# usb_converter.net
KiCad netlist of a schematic drawn in Altium Designer
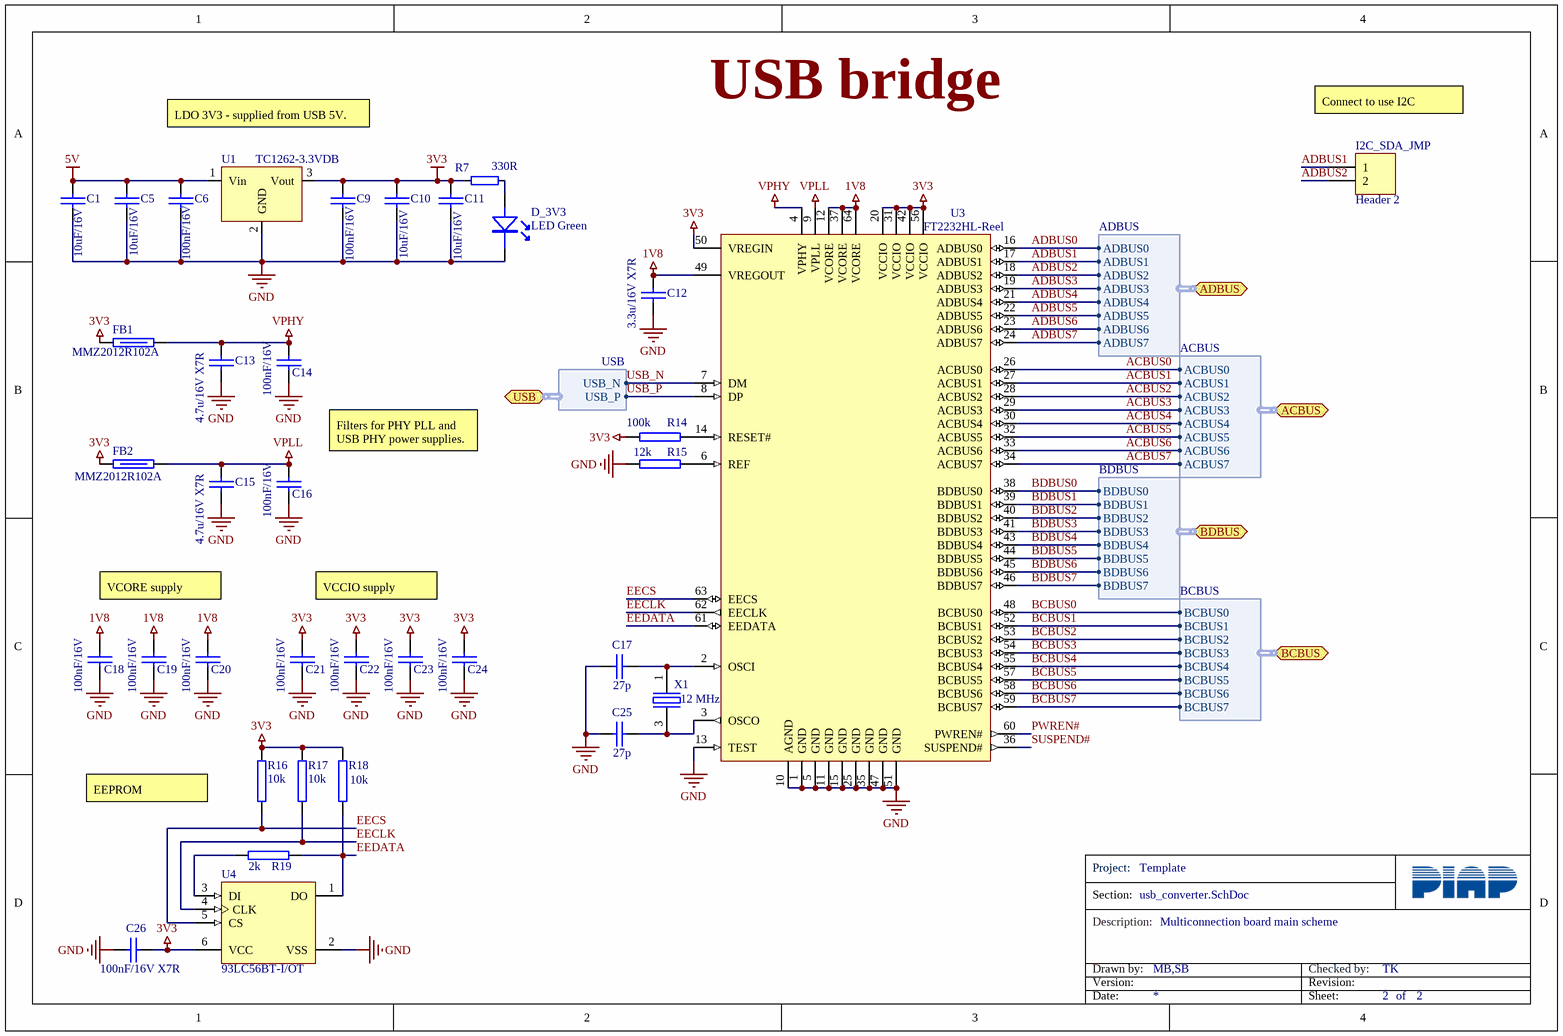
[diagram p0: usb_converter.SchDoc]

(export (version "E")
  (design (tool "Eeschema 10.0.6"))
  (components
    (comp (ref "C1")
      (value "10uF/16V")
      (footprint "packages:0603")
      (description "10uF,16V,0603,X5R, 10%")
      (fields (field (name "TOLERANCE") "10%"))
      (libsource (lib "cap_ceramic") (part "100nF/16V/0603"))
    )
    (comp (ref "C5")
      (value "10uF/16V")
      (footprint "packages:0603")
      (description "10uF,16V,0603,X5R, 10%")
      (fields (field (name "TOLERANCE") "10%"))
      (libsource (lib "cap_ceramic") (part "100nF/16V/0603"))
    )
    (comp (ref "C6")
      (value "100nF/16V")
      (footprint "packages:0603")
      (description "100nF,16V,0603,,X7R")
      (fields (field (name "TOLERANCE") "10%"))
      (libsource (lib "cap_ceramic") (part "100nF/16V/0603"))
    )
    (comp (ref "C9")
      (value "100nF/16V")
      (footprint "packages:0603")
      (description "100nF,16V,0603,,X7R")
      (fields (field (name "TOLERANCE") "10%"))
      (libsource (lib "cap_ceramic") (part "100nF/16V/0603"))
    )
    (comp (ref "C10")
      (value "10uF/16V")
      (footprint "packages:0603")
      (description "10uF,16V,0603,X5R, 10%")
      (fields (field (name "TOLERANCE") "10%"))
      (libsource (lib "cap_ceramic") (part "100nF/16V/0603"))
    )
    (comp (ref "C11")
      (value "10uF/16V")
      (footprint "packages:0603")
      (description "10uF,16V,0603,X5R, 10%")
      (fields (field (name "TOLERANCE") "10%"))
      (libsource (lib "cap_ceramic") (part "100nF/16V/0603"))
    )
    (comp (ref "C12")
      (value "3.3u/16V X7R")
      (footprint "packages:0805")
      (description "Chip Capacitor 3.3u/16V X7R")
      (fields (field (name "EMAIL") "AGrabowska@farnell.com"))
      (libsource (lib "capacitors") (part "n100"))
    )
    (comp (ref "C13")
      (value "4.7u/16V X7R")
      (footprint "packages:0805")
      (description "Chip Capacitor 4.7u/16V X7R")
      (fields (field (name "EMAIL") "AGrabowska@farnell.com"))
      (libsource (lib "capacitors") (part "n100"))
    )
    (comp (ref "C14")
      (value "100nF/16V")
      (footprint "packages:0603")
      (description "NS")
      (fields (field (name "EMAIL") "AGrabowska@farnell.com"))
      (libsource (lib "capacitors") (part "n100"))
    )
    (comp (ref "C15")
      (value "4.7u/16V X7R")
      (footprint "packages:0805")
      (description "Chip Capacitor 4.7u/16V X7R")
      (fields (field (name "EMAIL") "AGrabowska@farnell.com"))
      (libsource (lib "capacitors") (part "n100"))
    )
    (comp (ref "C16")
      (value "100nF/16V")
      (footprint "packages:0603")
      (description "NS")
      (fields (field (name "EMAIL") "AGrabowska@farnell.com"))
      (libsource (lib "capacitors") (part "n100"))
    )
    (comp (ref "C17")
      (value "27p")
      (footprint "packages:0603")
      (description "NS")
      (fields (field (name "EMAIL") "AGrabowska@farnell.com"))
      (libsource (lib "capacitors") (part "n100"))
    )
    (comp (ref "C18")
      (value "100nF/16V")
      (footprint "packages:0603")
      (description "NS")
      (fields (field (name "EMAIL") "AGrabowska@farnell.com"))
      (libsource (lib "capacitors") (part "n100"))
    )
    (comp (ref "C19")
      (value "100nF/16V")
      (footprint "packages:0603")
      (description "NS")
      (fields (field (name "EMAIL") "AGrabowska@farnell.com"))
      (libsource (lib "capacitors") (part "n100"))
    )
    (comp (ref "C20")
      (value "100nF/16V")
      (footprint "packages:0603")
      (description "NS")
      (fields (field (name "EMAIL") "AGrabowska@farnell.com"))
      (libsource (lib "capacitors") (part "n100"))
    )
    (comp (ref "C21")
      (value "100nF/16V")
      (footprint "packages:0603")
      (description "NS")
      (fields (field (name "EMAIL") "AGrabowska@farnell.com"))
      (libsource (lib "capacitors") (part "n100"))
    )
    (comp (ref "C22")
      (value "100nF/16V")
      (footprint "packages:0603")
      (description "NS")
      (fields (field (name "EMAIL") "AGrabowska@farnell.com"))
      (libsource (lib "capacitors") (part "n100"))
    )
    (comp (ref "C23")
      (value "100nF/16V")
      (footprint "packages:0603")
      (description "NS")
      (fields (field (name "EMAIL") "AGrabowska@farnell.com"))
      (libsource (lib "capacitors") (part "n100"))
    )
    (comp (ref "C24")
      (value "100nF/16V")
      (footprint "packages:0603")
      (description "NS")
      (fields (field (name "EMAIL") "AGrabowska@farnell.com"))
      (libsource (lib "capacitors") (part "n100"))
    )
    (comp (ref "C25")
      (value "27p")
      (footprint "packages:0603")
      (description "NS")
      (fields (field (name "EMAIL") "AGrabowska@farnell.com"))
      (libsource (lib "capacitors") (part "n100"))
    )
    (comp (ref "C26")
      (value "100nF/16V X7R")
      (footprint "packages:0805")
      (description "Chip Capacitor 100nF/16V X7R")
      (fields (field (name "EMAIL") "AGrabowska@farnell.com"))
      (libsource (lib "capacitors") (part "n100"))
    )
    (comp (ref "D_3V3")
      (value "LED Green")
      (footprint "packages:LED SMD 0805")
      (description "LED Green 0805")
      (fields (field (name "MANUFACTURER PART NUMBER") "KP-2012SGD"))
      (libsource (lib "diod_led") (part "led_0805_green"))
    )
    (comp (ref "FB1")
      (value "MMZ2012R102A")
      (footprint "packages:0805")
      (description "Chip ferrite bead 500mA")
      (libsource (lib "ind_filter") (part "MMZ2012R102A"))
    )
    (comp (ref "FB2")
      (value "MMZ2012R102A")
      (footprint "packages:0805")
      (description "Chip ferrite bead 500mA")
      (libsource (lib "ind_filter") (part "MMZ2012R102A"))
    )
    (comp (ref "I2C_SDA_JMP")
      (value "Header 2")
      (footprint "HDR1X2")
      (description "Header, 2-Pin,  2.54mm")
      (libsource (lib "connectors") (part "Header 2"))
    )
    (comp (ref "R7")
      (value "330R")
      (footprint "packages:0603")
      (description "Chip Resistor 0402")
      (fields (field (name "TOLERANCE") "1%"))
      (libsource (lib "res_std") (part "res_0603"))
    )
    (comp (ref "R14")
      (value "100k")
      (footprint "packages:0603")
      (description "Chip Resistor 100k O.25W")
      (libsource (lib "resistors") (part "k100"))
    )
    (comp (ref "R15")
      (value "12k")
      (footprint "packages:0603")
      (description "Chip Resistor 0.25W")
      (libsource (lib "resistors") (part "k100"))
    )
    (comp (ref "R16")
      (value "10k")
      (footprint "packages:0603")
      (description "Chip Resistor 0Ohm 0.25W")
      (libsource (lib "resistors") (part "k100"))
    )
    (comp (ref "R17")
      (value "10k")
      (footprint "packages:0603")
      (description "Chip Resistor 0Ohm 0.25W")
      (libsource (lib "resistors") (part "k100"))
    )
    (comp (ref "R18")
      (value "10k")
      (footprint "packages:0603")
      (description "Chip Resistor 0Ohm 0.25W")
      (libsource (lib "resistors") (part "k100"))
    )
    (comp (ref "R19")
      (value "2k")
      (footprint "packages:0603")
      (description "Chip Resistor 0.25W")
      (libsource (lib "resistors") (part "k100"))
    )
    (comp (ref "U1")
      (value "TC1262-3.3VDB")
      (footprint "packages:SOT223")
      (description "3-Terminal 3.3V 500mA Regulator")
      (fields (field (name "MANUFACTURER") "MICROCHIP"))
      (libsource (lib "pwr_linear") (part "TC1262-3.3VDB"))
    )
    (comp (ref "U3")
      (value "FT2232HL-Reel")
      (footprint "LQFP-64_L")
      (description "Dual High Speed USB To Multipurpose UART/FIFO IC, LQFP-64, Tape and Reel")
      (libsource (lib "Altium Content Vault") (part "COM-UART-FT2232H-LQFP64"))
    )
    (comp (ref "U4")
      (value "93LC56BT-I/OT")
      (footprint "SOT-23-OT6_L")
      (description "2K, 128x16-bit, 2.5V Microwire Serial EEPROM, 6-Pin SOT-23, Industrial Temperature, Tape and Reel")
      (libsource (lib "Altium Content Vault") (part "MEM-SEEPROM-93AA46B-OT-6"))
    )
    (comp (ref "X1")
      (value "12 MHz")
      (footprint "ABM8G")
      (description "ABRACON  ABM8G-12.000MHZ  CRYSTAL, 12MHZ, 10PF, 3.2 X 2.5MM")
      (fields (field (name "MANUFACTURER") "ABRACON"))
      (libsource (lib "crystal") (part "ABM8G-12.000MHZ-4Y-T3"))
    )
  )
  (nets
    (net (code "6") (name "/ACBUS0") (class "Default")
      (node (ref "U3") (pin "26") (pinfunction "ACBUS0_26") (pintype "bidirectional"))
    )
    (net (code "7") (name "/ACBUS1") (class "Default")
      (node (ref "U3") (pin "27") (pinfunction "ACBUS1_27") (pintype "bidirectional"))
    )
    (net (code "8") (name "/ACBUS2") (class "Default")
      (node (ref "U3") (pin "28") (pinfunction "ACBUS2_28") (pintype "bidirectional"))
    )
    (net (code "9") (name "/ACBUS3") (class "Default")
      (node (ref "U3") (pin "29") (pinfunction "ACBUS3_29") (pintype "bidirectional"))
    )
    (net (code "10") (name "/ACBUS4") (class "Default")
      (node (ref "U3") (pin "30") (pinfunction "ACBUS4_30") (pintype "bidirectional"))
    )
    (net (code "11") (name "/ACBUS5") (class "Default")
      (node (ref "U3") (pin "32") (pinfunction "ACBUS5_32") (pintype "bidirectional"))
    )
    (net (code "12") (name "/ACBUS6") (class "Default")
      (node (ref "U3") (pin "33") (pinfunction "ACBUS6_33") (pintype "bidirectional"))
    )
    (net (code "13") (name "/ACBUS7") (class "Default")
      (node (ref "U3") (pin "34") (pinfunction "ACBUS7_34") (pintype "bidirectional"))
    )
    (net (code "14") (name "/ADBUS0") (class "Default")
      (node (ref "U3") (pin "16") (pinfunction "ADBUS0_16") (pintype "bidirectional"))
    )
    (net (code "15") (name "/ADBUS1") (class "Default")
      (node (ref "I2C_SDA_JMP") (pin "1") (pinfunction "1_1") (pintype "passive"))
      (node (ref "U3") (pin "17") (pinfunction "ADBUS1_17") (pintype "bidirectional"))
    )
    (net (code "16") (name "/ADBUS2") (class "Default")
      (node (ref "I2C_SDA_JMP") (pin "2") (pinfunction "2_2") (pintype "passive"))
      (node (ref "U3") (pin "18") (pinfunction "ADBUS2_18") (pintype "bidirectional"))
    )
    (net (code "17") (name "/ADBUS3") (class "Default")
      (node (ref "U3") (pin "19") (pinfunction "ADBUS3_19") (pintype "bidirectional"))
    )
    (net (code "18") (name "/ADBUS4") (class "Default")
      (node (ref "U3") (pin "21") (pinfunction "ADBUS4_21") (pintype "bidirectional"))
    )
    (net (code "19") (name "/ADBUS5") (class "Default")
      (node (ref "U3") (pin "22") (pinfunction "ADBUS5_22") (pintype "bidirectional"))
    )
    (net (code "20") (name "/ADBUS6") (class "Default")
      (node (ref "U3") (pin "23") (pinfunction "ADBUS6_23") (pintype "bidirectional"))
    )
    (net (code "21") (name "/ADBUS7") (class "Default")
      (node (ref "U3") (pin "24") (pinfunction "ADBUS7_24") (pintype "bidirectional"))
    )
    (net (code "22") (name "/BCBUS0") (class "Default")
      (node (ref "U3") (pin "48") (pinfunction "BCBUS0_48") (pintype "bidirectional"))
    )
    (net (code "23") (name "/BCBUS1") (class "Default")
      (node (ref "U3") (pin "52") (pinfunction "BCBUS1_52") (pintype "bidirectional"))
    )
    (net (code "24") (name "/BCBUS2") (class "Default")
      (node (ref "U3") (pin "53") (pinfunction "BCBUS2_53") (pintype "bidirectional"))
    )
    (net (code "25") (name "/BCBUS3") (class "Default")
      (node (ref "U3") (pin "54") (pinfunction "BCBUS3_54") (pintype "bidirectional"))
    )
    (net (code "26") (name "/BCBUS4") (class "Default")
      (node (ref "U3") (pin "55") (pinfunction "BCBUS4_55") (pintype "bidirectional"))
    )
    (net (code "27") (name "/BCBUS5") (class "Default")
      (node (ref "U3") (pin "57") (pinfunction "BCBUS5_57") (pintype "bidirectional"))
    )
    (net (code "28") (name "/BCBUS6") (class "Default")
      (node (ref "U3") (pin "58") (pinfunction "BCBUS6_58") (pintype "bidirectional"))
    )
    (net (code "29") (name "/BCBUS7") (class "Default")
      (node (ref "U3") (pin "59") (pinfunction "BCBUS7_59") (pintype "bidirectional"))
    )
    (net (code "30") (name "/BDBUS0") (class "Default")
      (node (ref "U3") (pin "38") (pinfunction "BDBUS0_38") (pintype "bidirectional"))
    )
    (net (code "31") (name "/BDBUS1") (class "Default")
      (node (ref "U3") (pin "39") (pinfunction "BDBUS1_39") (pintype "bidirectional"))
    )
    (net (code "32") (name "/BDBUS2") (class "Default")
      (node (ref "U3") (pin "40") (pinfunction "BDBUS2_40") (pintype "bidirectional"))
    )
    (net (code "33") (name "/BDBUS3") (class "Default")
      (node (ref "U3") (pin "41") (pinfunction "BDBUS3_41") (pintype "bidirectional"))
    )
    (net (code "34") (name "/BDBUS4") (class "Default")
      (node (ref "U3") (pin "43") (pinfunction "BDBUS4_43") (pintype "bidirectional"))
    )
    (net (code "35") (name "/BDBUS5") (class "Default")
      (node (ref "U3") (pin "44") (pinfunction "BDBUS5_44") (pintype "bidirectional"))
    )
    (net (code "36") (name "/BDBUS6") (class "Default")
      (node (ref "U3") (pin "45") (pinfunction "BDBUS6_45") (pintype "bidirectional"))
    )
    (net (code "37") (name "/BDBUS7") (class "Default")
      (node (ref "U3") (pin "46") (pinfunction "BDBUS7_46") (pintype "bidirectional"))
    )
    (net (code "38") (name "/EECLK") (class "Default")
      (node (ref "R17") (pin "2") (pinfunction "2_2") (pintype "passive"))
      (node (ref "U3") (pin "62") (pinfunction "EECLK_62") (pintype "output"))
      (node (ref "U4") (pin "4") (pinfunction "CLK_4") (pintype "input"))
    )
    (net (code "39") (name "/EECS") (class "Default")
      (node (ref "R16") (pin "2") (pinfunction "2_2") (pintype "passive"))
      (node (ref "U3") (pin "63") (pinfunction "EECS_63") (pintype "bidirectional"))
      (node (ref "U4") (pin "5") (pinfunction "CS_5") (pintype "input"))
    )
    (net (code "40") (name "/EEDATA") (class "Default")
      (node (ref "R18") (pin "2") (pinfunction "2_2") (pintype "passive"))
      (node (ref "R19") (pin "1") (pinfunction "1_1") (pintype "passive"))
      (node (ref "U3") (pin "61") (pinfunction "EEDATA_61") (pintype "bidirectional"))
      (node (ref "U4") (pin "1") (pinfunction "DO_1") (pintype "tri_state"))
    )
    (net (code "41") (name "/PWREN#") (class "Default")
      (node (ref "U3") (pin "60") (pinfunction "PWREN#_60") (pintype "output"))
    )
    (net (code "42") (name "/SUSPEND#") (class "Default")
      (node (ref "U3") (pin "36") (pinfunction "SUSPEND#_36") (pintype "output"))
    )
    (net (code "43") (name "/USB_N") (class "Default")
      (node (ref "U3") (pin "7") (pinfunction "DM_7") (pintype "input"))
    )
    (net (code "44") (name "/USB_P") (class "Default")
      (node (ref "U3") (pin "8") (pinfunction "DP_8") (pintype "input"))
    )
    (net (code "50") (name "1V8") (class "Default")
      (node (ref "C12") (pin "1") (pinfunction "1_1") (pintype "passive"))
      (node (ref "C18") (pin "1") (pinfunction "1_1") (pintype "passive"))
      (node (ref "C19") (pin "1") (pinfunction "1_1") (pintype "passive"))
      (node (ref "C20") (pin "1") (pinfunction "1_1") (pintype "passive"))
      (node (ref "U3") (pin "12") (pinfunction "VCORE_12") (pintype "power_in"))
      (node (ref "U3") (pin "37") (pinfunction "VCORE_37") (pintype "power_in"))
      (node (ref "U3") (pin "49") (pinfunction "VREGOUT_49") (pintype "power_in"))
      (node (ref "U3") (pin "64") (pinfunction "VCORE_64") (pintype "power_in"))
    )
    (net (code "51") (name "3V3") (class "Default")
      (node (ref "C10") (pin "2") (pinfunction "2_2") (pintype "passive"))
      (node (ref "C11") (pin "2") (pinfunction "2_2") (pintype "passive"))
      (node (ref "C21") (pin "1") (pinfunction "1_1") (pintype "passive"))
      (node (ref "C22") (pin "1") (pinfunction "1_1") (pintype "passive"))
      (node (ref "C23") (pin "1") (pinfunction "1_1") (pintype "passive"))
      (node (ref "C24") (pin "1") (pinfunction "1_1") (pintype "passive"))
      (node (ref "C26") (pin "2") (pinfunction "2_2") (pintype "passive"))
      (node (ref "C9") (pin "2") (pinfunction "2_2") (pintype "passive"))
      (node (ref "FB1") (pin "2") (pinfunction "2_2") (pintype "passive"))
      (node (ref "FB2") (pin "2") (pinfunction "2_2") (pintype "passive"))
      (node (ref "R14") (pin "2") (pinfunction "2_2") (pintype "passive"))
      (node (ref "R16") (pin "1") (pinfunction "1_1") (pintype "passive"))
      (node (ref "R17") (pin "1") (pinfunction "1_1") (pintype "passive"))
      (node (ref "R18") (pin "1") (pinfunction "1_1") (pintype "passive"))
      (node (ref "R7") (pin "1") (pinfunction "1_1") (pintype "passive"))
      (node (ref "U1") (pin "3") (pinfunction "Vout_3") (pintype "passive"))
      (node (ref "U3") (pin "20") (pinfunction "VCCIO_20") (pintype "power_in"))
      (node (ref "U3") (pin "31") (pinfunction "VCCIO_31") (pintype "power_in"))
      (node (ref "U3") (pin "42") (pinfunction "VCCIO_42") (pintype "power_in"))
      (node (ref "U3") (pin "50") (pinfunction "VREGIN_50") (pintype "power_in"))
      (node (ref "U3") (pin "56") (pinfunction "VCCIO_56") (pintype "power_in"))
      (node (ref "U4") (pin "6") (pinfunction "VCC_6") (pintype "power_in"))
    )
    (net (code "52") (name "5V") (class "Default")
      (node (ref "C1") (pin "2") (pinfunction "2_2") (pintype "passive"))
      (node (ref "C5") (pin "2") (pinfunction "2_2") (pintype "passive"))
      (node (ref "C6") (pin "2") (pinfunction "2_2") (pintype "passive"))
      (node (ref "U1") (pin "1") (pinfunction "Vin_1") (pintype "passive"))
    )
    (net (code "53") (name "GND") (class "Default")
      (node (ref "C1") (pin "1") (pinfunction "1_1") (pintype "passive"))
      (node (ref "C10") (pin "1") (pinfunction "1_1") (pintype "passive"))
      (node (ref "C11") (pin "1") (pinfunction "1_1") (pintype "passive"))
      (node (ref "C12") (pin "2") (pinfunction "2_2") (pintype "passive"))
      (node (ref "C13") (pin "2") (pinfunction "2_2") (pintype "passive"))
      (node (ref "C14") (pin "2") (pinfunction "2_2") (pintype "passive"))
      (node (ref "C15") (pin "2") (pinfunction "2_2") (pintype "passive"))
      (node (ref "C16") (pin "2") (pinfunction "2_2") (pintype "passive"))
      (node (ref "C17") (pin "2") (pinfunction "2_2") (pintype "passive"))
      (node (ref "C18") (pin "2") (pinfunction "2_2") (pintype "passive"))
      (node (ref "C19") (pin "2") (pinfunction "2_2") (pintype "passive"))
      (node (ref "C20") (pin "2") (pinfunction "2_2") (pintype "passive"))
      (node (ref "C21") (pin "2") (pinfunction "2_2") (pintype "passive"))
      (node (ref "C22") (pin "2") (pinfunction "2_2") (pintype "passive"))
      (node (ref "C23") (pin "2") (pinfunction "2_2") (pintype "passive"))
      (node (ref "C24") (pin "2") (pinfunction "2_2") (pintype "passive"))
      (node (ref "C25") (pin "2") (pinfunction "2_2") (pintype "passive"))
      (node (ref "C26") (pin "1") (pinfunction "1_1") (pintype "passive"))
      (node (ref "C5") (pin "1") (pinfunction "1_1") (pintype "passive"))
      (node (ref "C6") (pin "1") (pinfunction "1_1") (pintype "passive"))
      (node (ref "C9") (pin "1") (pinfunction "1_1") (pintype "passive"))
      (node (ref "D_3V3") (pin "2") (pinfunction "2_2") (pintype "passive"))
      (node (ref "R15") (pin "2") (pinfunction "2_2") (pintype "passive"))
      (node (ref "U1") (pin "2") (pinfunction "GND_2") (pintype "passive"))
      (node (ref "U3") (pin "1") (pinfunction "GND_1") (pintype "power_in"))
      (node (ref "U3") (pin "10") (pinfunction "AGND_10") (pintype "power_in"))
      (node (ref "U3") (pin "11") (pinfunction "GND_11") (pintype "power_in"))
      (node (ref "U3") (pin "13") (pinfunction "TEST_13") (pintype "input"))
      (node (ref "U3") (pin "15") (pinfunction "GND_15") (pintype "power_in"))
      (node (ref "U3") (pin "25") (pinfunction "GND_25") (pintype "power_in"))
      (node (ref "U3") (pin "35") (pinfunction "GND_35") (pintype "power_in"))
      (node (ref "U3") (pin "47") (pinfunction "GND_47") (pintype "power_in"))
      (node (ref "U3") (pin "5") (pinfunction "GND_5") (pintype "power_in"))
      (node (ref "U3") (pin "51") (pinfunction "GND_51") (pintype "power_in"))
      (node (ref "U4") (pin "2") (pinfunction "VSS_2") (pintype "power_in"))
    )
    (net (code "54") (name "Net-(D_3V3-Pad1)") (class "Default")
      (node (ref "D_3V3") (pin "1") (pinfunction "1_1") (pintype "passive"))
      (node (ref "R7") (pin "2") (pinfunction "2_2") (pintype "passive"))
    )
    (net (code "55") (name "Net-(U3-OSCI)") (class "Default")
      (node (ref "C17") (pin "1") (pinfunction "1_1") (pintype "passive"))
      (node (ref "U3") (pin "2") (pinfunction "OSCI_2") (pintype "input"))
      (node (ref "X1") (pin "1") (pinfunction "1_1") (pintype "passive"))
    )
    (net (code "56") (name "Net-(U3-OSCO)") (class "Default")
      (node (ref "C25") (pin "1") (pinfunction "1_1") (pintype "passive"))
      (node (ref "U3") (pin "3") (pinfunction "OSCO_3") (pintype "output"))
      (node (ref "X1") (pin "3") (pinfunction "3_3") (pintype "passive"))
    )
    (net (code "57") (name "Net-(U3-REF)") (class "Default")
      (node (ref "R15") (pin "1") (pinfunction "1_1") (pintype "passive"))
      (node (ref "U3") (pin "6") (pinfunction "REF_6") (pintype "input"))
    )
    (net (code "58") (name "Net-(U3-RESET#)") (class "Default")
      (node (ref "R14") (pin "1") (pinfunction "1_1") (pintype "passive"))
      (node (ref "U3") (pin "14") (pinfunction "RESET#_14") (pintype "input"))
    )
    (net (code "59") (name "Net-(U4-DI)") (class "Default")
      (node (ref "R19") (pin "2") (pinfunction "2_2") (pintype "passive"))
      (node (ref "U4") (pin "3") (pinfunction "DI_3") (pintype "input"))
    )
    (net (code "60") (name "VPHY") (class "Default")
      (node (ref "C13") (pin "1") (pinfunction "1_1") (pintype "passive"))
      (node (ref "C14") (pin "1") (pinfunction "1_1") (pintype "passive"))
      (node (ref "FB1") (pin "1") (pinfunction "1_1") (pintype "passive"))
      (node (ref "U3") (pin "4") (pinfunction "VPHY_4") (pintype "power_in"))
    )
    (net (code "61") (name "VPLL") (class "Default")
      (node (ref "C15") (pin "1") (pinfunction "1_1") (pintype "passive"))
      (node (ref "C16") (pin "1") (pinfunction "1_1") (pintype "passive"))
      (node (ref "FB2") (pin "1") (pinfunction "1_1") (pintype "passive"))
      (node (ref "U3") (pin "9") (pinfunction "VPLL_9") (pintype "power_in"))
    )
  )
)
